# Power_Supply.net
KiCad netlist of a schematic drawn in Altium Designer
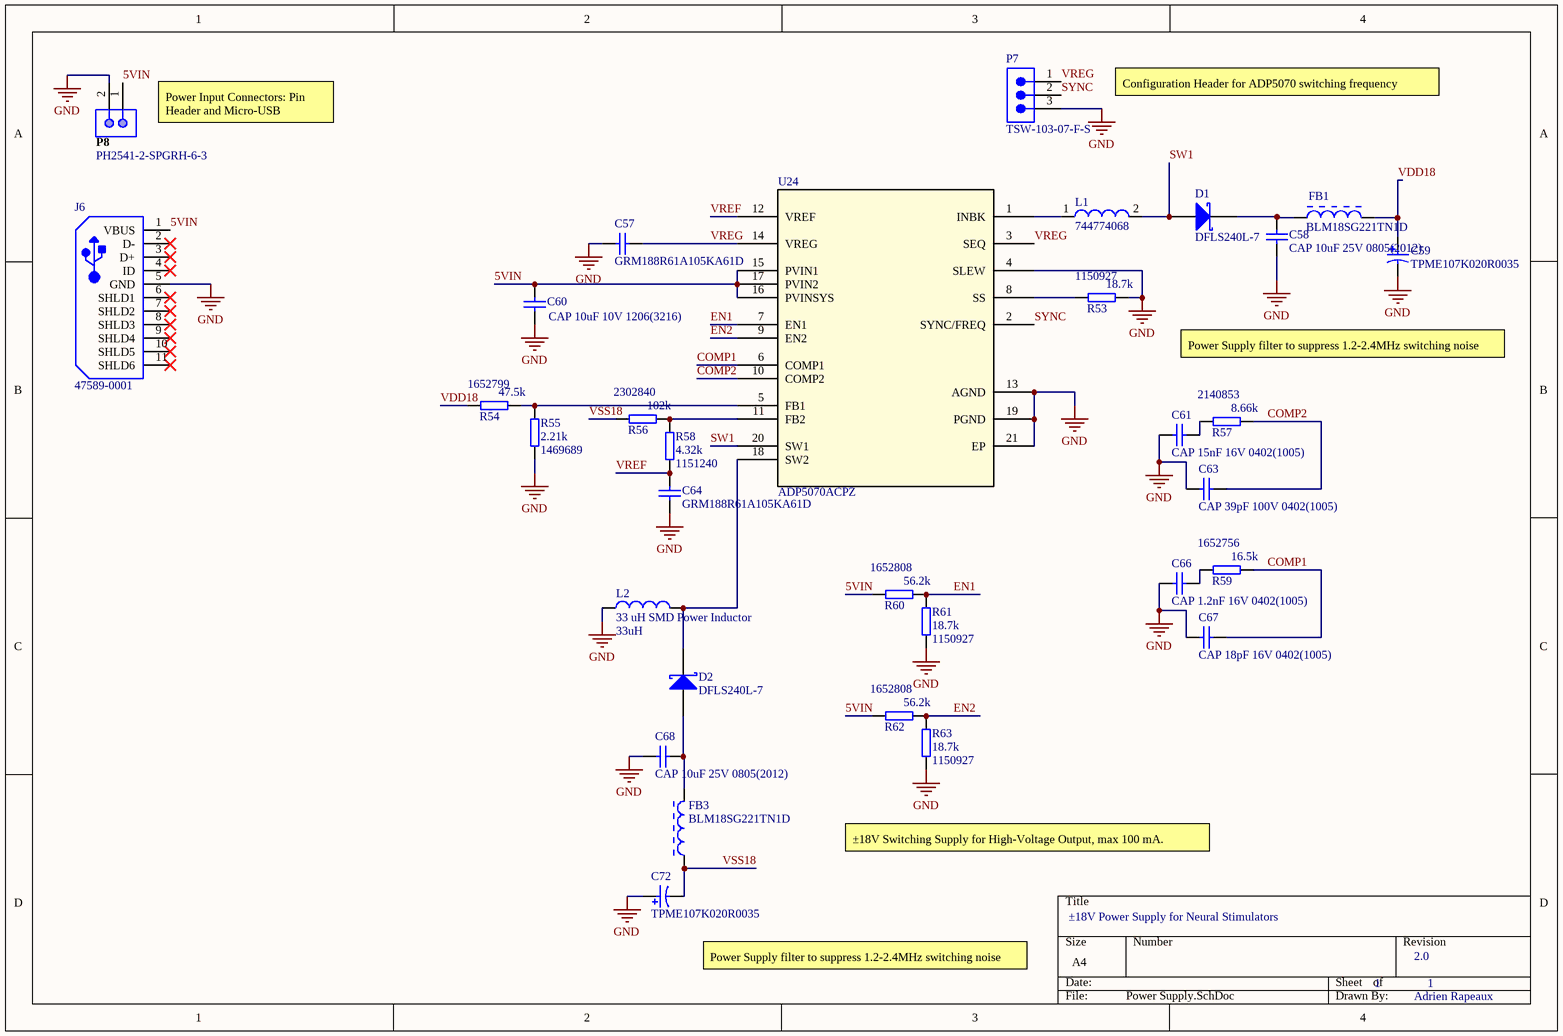
[diagram p0: Power Supply.SchDoc]

(export (version "E")
  (design (tool "Eeschema 10.0.6"))
  (components
    (comp (ref "C57")
      (value "GRM188R61A105KA61D")
      (footprint "CAPC1608X90X35LL10T15")
      (description "Chip Capacitor, 1 uF, +/- 10%, 10 V, -55 to 85 degC, 0603 (1608 Metric), RoHS, Tape and Reel")
      (fields (field (name "MANUFACTURER") "Murata") (field (name "TOLERANCE") "10%"))
      (libsource (lib "Altium Content Vault") (part "CAP-NP-2"))
    )
    (comp (ref "C58")
      (value "CAP 10uF 25V 0805(2012)")
      (footprint "CAPC0805(2012)145_N")
      (description "CAP 10uF 25V ±10% 0805 (2012 Metric) Thickness 1.45mm SMD")
      (fields (field (name "TOLERANCE") "Â±10%"))
      (libsource (lib "Altium Content Vault") (part "CAP"))
    )
    (comp (ref "C59")
      (value "TPME107K020R0035")
      (footprint "CAPMP7344X31-T_V")
      (description "Low ESR, 100 uF, 25 V, +/- 10%, -55 to 125 degC, 2-Pin SMD, RoHS, Tape and Reel")
      (fields (field (name "TOLERANCE") "20%") (field (name "MANUFACTURER") "AVX"))
      (libsource (lib "Altium Content Vault") (part "CAP-P-2"))
    )
    (comp (ref "C60")
      (value "CAP 10uF 10V 1206(3216)")
      (footprint "CAPC1206(3216)130_L")
      (description "CAP 10uF 10V -20% to +80% 1206 (3216 Metric) Thickness 1.3mm SMD")
      (fields (field (name "TOLERANCE") "-20% to +80%"))
      (libsource (lib "Altium Content Vault") (part "CAP"))
    )
    (comp (ref "C61")
      (value "CAP 15nF 16V 0402(1005)")
      (footprint "CAPC0402(1005)60_L")
      (description "CAP 15nF 16V ±10% 0402 (1005 Metric) Thickness 0.6mm SMD")
      (fields (field (name "TOLERANCE") "Â±10%"))
      (libsource (lib "Altium Content Vault") (part "CAP"))
    )
    (comp (ref "C63")
      (value "CAP 39pF 100V 0402(1005)")
      (footprint "CAPC0402(1005)60_L")
      (description "CAP 39pF 100V ±10% 0402 (1005 Metric) Thickness 0.6mm SMD")
      (fields (field (name "TOLERANCE") "Â±10%"))
      (libsource (lib "Altium Content Vault") (part "CAP"))
    )
    (comp (ref "C64")
      (value "GRM188R61A105KA61D")
      (footprint "CAPC1608X90X35LL10T15")
      (description "Chip Capacitor, 1 uF, +/- 10%, 10 V, -55 to 85 degC, 0603 (1608 Metric), RoHS, Tape and Reel")
      (fields (field (name "MANUFACTURER") "Murata") (field (name "TOLERANCE") "10%"))
      (libsource (lib "Altium Content Vault") (part "CAP-NP-2"))
    )
    (comp (ref "C66")
      (value "CAP 1.2nF 16V 0402(1005)")
      (footprint "CAPC0402(1005)60_L")
      (description "CAP 1.2nF 16V ±10% 0402 (1005 Metric) Thickness 0.6mm SMD")
      (fields (field (name "TOLERANCE") "Â±10%"))
      (libsource (lib "Altium Content Vault") (part "CAP"))
    )
    (comp (ref "C67")
      (value "CAP 18pF 16V 0402(1005)")
      (footprint "CAPC0402(1005)60_L")
      (description "CAP 18pF 16V ±10% 0402 (1005 Metric) Thickness 0.6mm SMD")
      (fields (field (name "TOLERANCE") "Â±10%"))
      (libsource (lib "Altium Content Vault") (part "CAP"))
    )
    (comp (ref "C68")
      (value "CAP 10uF 25V 0805(2012)")
      (footprint "CAPC0805(2012)145_N")
      (description "CAP 10uF 25V ±10% 0805 (2012 Metric) Thickness 1.45mm SMD")
      (fields (field (name "TOLERANCE") "Â±10%"))
      (libsource (lib "Altium Content Vault") (part "CAP"))
    )
    (comp (ref "C72")
      (value "TPME107K020R0035")
      (footprint "CAPMP7344X31-T_V")
      (description "Low ESR, 100 uF, 25 V, +/- 10%, -55 to 125 degC, 2-Pin SMD, RoHS, Tape and Reel")
      (fields (field (name "TOLERANCE") "20%") (field (name "MANUFACTURER") "AVX"))
      (libsource (lib "Altium Content Vault") (part "CAP-P-2"))
    )
    (comp (ref "D1")
      (value "DFLS240L-7")
      (footprint "DIOD-POWERDI123-2_A_V")
      (description "Low VF Schottky Barrier Rectifier, 2 A, 40 V, -55 to 125 degC, 2-Pin SMD, RoHS, Tape and Reel")
      (fields (field (name "MANUFACTURER") "Diodes Inc"))
      (libsource (lib "Altium Content Vault") (part "DSKY-AK-2"))
    )
    (comp (ref "D2")
      (value "DFLS240L-7")
      (footprint "DIOD-POWERDI123-2_A_V")
      (description "Low VF Schottky Barrier Rectifier, 2 A, 40 V, -55 to 125 degC, 2-Pin SMD, RoHS, Tape and Reel")
      (fields (field (name "MANUFACTURER") "Diodes Inc"))
      (libsource (lib "Altium Content Vault") (part "DSKY-AK-2"))
    )
    (comp (ref "FB1")
      (value "BLM18SG221TN1D")
      (footprint "MURA-BLM18SG-B25-CHIP-2_V1")
      (fields (field (name "MANUFACTURER") "Murata"))
      (libsource (lib "Altium Content Vault") (part "MURA-FB-2"))
    )
    (comp (ref "FB3")
      (value "BLM18SG221TN1D")
      (footprint "MURA-BLM18SG-B25-CHIP-2_V1")
      (fields (field (name "MANUFACTURER") "Murata"))
      (libsource (lib "Altium Content Vault") (part "MURA-FB-2"))
    )
    (comp (ref "J6")
      (value "47589-0001")
      (footprint "MOLX-47589-0001_V")
      (description "Right Angle Female Type AB Micro USB Connector, 30 V, 1.8 A, -30 to 85 degC, RoHS, Tape and Reel")
      (fields (field (name "MANUFACTURER") "Molex"))
      (libsource (lib "Altium Content Vault") (part "USB-5-6SHLD"))
    )
    (comp (ref "L1")
      (value "744774068")
      (footprint "WE-PD2-M")
      (description "SMD Power Inductor WE-PD2, L = 6.80 µH")
      (libsource (lib "Altium Content Vault") (part "PAS-IND-INDUCTOR-2"))
    )
    (comp (ref "L2")
      (value "33 uH SMD Power Inductor")
      (footprint "LPS6235 SERIES")
      (description "33 uH SMD Power Inductor, 1A RMS, 1.4A Isat, Shielded, LPS6235 Series, Coilcraft")
      (fields (field (name "ALTIUM_VALUE") "33uH") (field (name "PUBLISHER") "Adrien Rapeaux"))
      (libsource (lib "ar5113_Altium_Library") (part "LPS6235-333MRB"))
    )
    (comp (ref "P7")
      (value "TSW-103-07-F-S")
      (footprint "SMTC-TSW-103-07-X-S")
      (description "0.025\" SQ Post Header, Through-hole, Vertical, -55 to 125 degC, 2.54 mm Pitch, 3-Pin, Male, RoHS")
      (fields (field (name "MANUFACTURER") "Samtec"))
      (libsource (lib "Altium Content Vault") (part "SMTC-TSW-103-X-X-S-X"))
    )
    (comp (ref "P8")
      (value "PH2541-2-SPGRH-6-3")
      (footprint "PH2541-2-SPGRH-6-3_V")
      (description "Male Header, Pitch 2.54mm, 2x1 Position, Mated Height 6mm, Tail Length 3mm")
      (libsource (lib "Altium Content Vault") (part "PCE-HDR-1P-M-R2"))
    )
    (comp (ref "R53")
      (value "18.7k")
      (footprint "RESC0402")
      (description "RES 18K7 0402 0.063W 1%")
      (fields
        (field (name "MANUFACTURER PART NUMBER") "CRCW040218K7FKTDBC")
        (field (name "MANUFACTURER") "VISHAY")
        (field (name "SUPPLIER PART NUMBER 2") "1150927")
      )
      (libsource (lib "Lib_MyProto") (part "myProto-12585"))
    )
    (comp (ref "R54")
      (value "47.5k")
      (footprint "RESC0402")
      (description "RES 47K5 0402 0.063W 1%")
      (fields
        (field (name "MANUFACTURER PART NUMBER") "CRCW040247K5FKTDBC")
        (field (name "MANUFACTURER") "VISHAY")
        (field (name "SUPPLIER PART NUMBER 2") "1652799")
      )
      (libsource (lib "Lib_MyProto") (part "myProto-12633"))
    )
    (comp (ref "R55")
      (value "2.21k")
      (footprint "RESC0402")
      (description "RES 2K21 0402 0.063W 1%")
      (fields
        (field (name "MANUFACTURER PART NUMBER") "CRCW04022K21FKTDBC")
        (field (name "MANUFACTURER") "VISHAY")
        (field (name "SUPPLIER PART NUMBER 1") "1469689")
      )
      (libsource (lib "Lib_MyProto") (part "myProto-12479"))
    )
    (comp (ref "R56")
      (value "102k")
      (footprint "RESC0402")
      (description "RES 102K 0402 0.063W 1%")
      (fields
        (field (name "MANUFACTURER PART NUMBER") "CRCW0402102KFKTDBC")
        (field (name "MANUFACTURER") "VISHAY")
        (field (name "SUPPLIER PART NUMBER 1") "2302840")
      )
      (libsource (lib "Lib_MyProto") (part "myProto-12671"))
    )
    (comp (ref "R57")
      (value "8.66k")
      (footprint "RESC0402")
      (description "RES 8K66 0402 0.063W 1%")
      (fields
        (field (name "MANUFACTURER PART NUMBER") "CRCW04028K66FKTDBC")
        (field (name "MANUFACTURER") "VISHAY")
        (field (name "SUPPLIER PART NUMBER 1") "2140853")
      )
      (libsource (lib "Lib_MyProto") (part "myProto-12549"))
    )
    (comp (ref "R58")
      (value "4.32k")
      (footprint "RESC0402")
      (description "RES 4K32 0402 0.063W 1%")
      (fields
        (field (name "MANUFACTURER PART NUMBER") "CRCW04024K32FKTDBC")
        (field (name "MANUFACTURER") "VISHAY")
        (field (name "SUPPLIER PART NUMBER 1") "1151240")
      )
      (libsource (lib "Lib_MyProto") (part "myProto-12514"))
    )
    (comp (ref "R59")
      (value "16.5k")
      (footprint "RESC0402")
      (description "RES 16K5 0402 0.063W 1%")
      (fields
        (field (name "MANUFACTURER PART NUMBER") "CRCW040216K5FKTDBC")
        (field (name "MANUFACTURER") "VISHAY")
        (field (name "SUPPLIER PART NUMBER 1") "1652756")
      )
      (libsource (lib "Lib_MyProto") (part "myProto-12579"))
    )
    (comp (ref "R60")
      (value "56.2k")
      (footprint "RESC0402")
      (description "RES 56K2 0402 0.063W 1%")
      (fields
        (field (name "MANUFACTURER PART NUMBER") "CRCW040256K2FKTDBC")
        (field (name "MANUFACTURER") "VISHAY")
        (field (name "SUPPLIER PART NUMBER 1") "1652808")
      )
      (libsource (lib "Lib_MyProto") (part "myProto-12642"))
    )
    (comp (ref "R61")
      (value "18.7k")
      (footprint "RESC0402")
      (description "RES 18K7 0402 0.063W 1%")
      (fields
        (field (name "MANUFACTURER PART NUMBER") "CRCW040218K7FKTDBC")
        (field (name "MANUFACTURER") "VISHAY")
        (field (name "SUPPLIER PART NUMBER 2") "1150927")
      )
      (libsource (lib "Lib_MyProto") (part "myProto-12585"))
    )
    (comp (ref "R62")
      (value "56.2k")
      (footprint "RESC0402")
      (description "RES 56K2 0402 0.063W 1%")
      (fields
        (field (name "MANUFACTURER PART NUMBER") "CRCW040256K2FKTDBC")
        (field (name "MANUFACTURER") "VISHAY")
        (field (name "SUPPLIER PART NUMBER 1") "1652808")
      )
      (libsource (lib "Lib_MyProto") (part "myProto-12642"))
    )
    (comp (ref "R63")
      (value "18.7k")
      (footprint "RESC0402")
      (description "RES 18K7 0402 0.063W 1%")
      (fields
        (field (name "MANUFACTURER PART NUMBER") "CRCW040218K7FKTDBC")
        (field (name "MANUFACTURER") "VISHAY")
        (field (name "SUPPLIER PART NUMBER 2") "1150927")
      )
      (libsource (lib "Lib_MyProto") (part "myProto-12585"))
    )
    (comp (ref "U24")
      (value "ADP5070ACPZ")
      (footprint "CP_20_8")
      (description "Imported")
      (libsource (lib "ar5113_Altium_Library") (part "ADP5070ACPZ"))
    )
  )
  (nets
    (net (code "1") (name "/5VIN") (class "Default")
      (node (ref "C60") (pin "2") (pinfunction "2_2") (pintype "passive"))
      (node (ref "J6") (pin "1") (pinfunction "VBUS_1") (pintype "passive"))
      (node (ref "P8") (pin "1") (pinfunction "1_1") (pintype "passive"))
      (node (ref "R60") (pin "2") (pinfunction "2_2") (pintype "passive"))
      (node (ref "R62") (pin "2") (pinfunction "2_2") (pintype "passive"))
      (node (ref "U24") (pin "15") (pinfunction "PVIN1_15") (pintype "passive"))
      (node (ref "U24") (pin "16") (pinfunction "PVINSYS_16") (pintype "passive"))
      (node (ref "U24") (pin "17") (pinfunction "PVIN2_17") (pintype "passive"))
    )
    (net (code "2") (name "/COMP1") (class "Default")
      (node (ref "C67") (pin "2") (pinfunction "2_2") (pintype "passive"))
      (node (ref "R59") (pin "1") (pinfunction "1_1") (pintype "passive"))
      (node (ref "U24") (pin "6") (pinfunction "COMP1_6") (pintype "passive"))
    )
    (net (code "3") (name "/COMP2") (class "Default")
      (node (ref "C63") (pin "2") (pinfunction "2_2") (pintype "passive"))
      (node (ref "R57") (pin "1") (pinfunction "1_1") (pintype "passive"))
      (node (ref "U24") (pin "10") (pinfunction "COMP2_10") (pintype "passive"))
    )
    (net (code "4") (name "/EN1") (class "Default")
      (node (ref "R60") (pin "1") (pinfunction "1_1") (pintype "passive"))
      (node (ref "R61") (pin "1") (pinfunction "1_1") (pintype "passive"))
      (node (ref "U24") (pin "7") (pinfunction "EN1_7") (pintype "passive"))
    )
    (net (code "5") (name "/EN2") (class "Default")
      (node (ref "R62") (pin "1") (pinfunction "1_1") (pintype "passive"))
      (node (ref "R63") (pin "1") (pinfunction "1_1") (pintype "passive"))
      (node (ref "U24") (pin "9") (pinfunction "EN2_9") (pintype "passive"))
    )
    (net (code "6") (name "/SW1") (class "Default")
      (node (ref "D1") (pin "1") (pinfunction "A_1") (pintype "passive"))
      (node (ref "L1") (pin "2") (pinfunction "2_2") (pintype "passive"))
      (node (ref "U24") (pin "20") (pinfunction "SW1_20") (pintype "passive"))
    )
    (net (code "7") (name "/SYNC") (class "Default")
      (node (ref "P7") (pin "2") (pinfunction "2_2") (pintype "passive"))
      (node (ref "U24") (pin "2") (pinfunction "SYNC/FREQ_2") (pintype "passive"))
    )
    (net (code "8") (name "/VDD18") (class "Default")
      (node (ref "C59") (pin "1") (pinfunction "1_1") (pintype "passive"))
      (node (ref "FB1") (pin "2") (pinfunction "2_2") (pintype "passive"))
      (node (ref "R54") (pin "2") (pinfunction "2_2") (pintype "passive"))
    )
    (net (code "9") (name "/VREF") (class "Default")
      (node (ref "C64") (pin "2") (pinfunction "2_2") (pintype "passive"))
      (node (ref "R58") (pin "2") (pinfunction "2_2") (pintype "passive"))
      (node (ref "U24") (pin "12") (pinfunction "VREF_12") (pintype "passive"))
    )
    (net (code "10") (name "/VREG") (class "Default")
      (node (ref "C57") (pin "2") (pinfunction "2_2") (pintype "passive"))
      (node (ref "P7") (pin "1") (pinfunction "1_1") (pintype "passive"))
      (node (ref "U24") (pin "14") (pinfunction "VREG_14") (pintype "passive"))
      (node (ref "U24") (pin "3") (pinfunction "SEQ_3") (pintype "passive"))
    )
    (net (code "11") (name "/VSS18") (class "Default")
      (node (ref "C72") (pin "2") (pinfunction "2_2") (pintype "passive"))
      (node (ref "FB3") (pin "1") (pinfunction "1_1") (pintype "passive"))
      (node (ref "R56") (pin "2") (pinfunction "2_2") (pintype "passive"))
    )
    (net (code "12") (name "GND") (class "Default")
      (node (ref "C57") (pin "1") (pinfunction "1_1") (pintype "passive"))
      (node (ref "C58") (pin "1") (pinfunction "1_1") (pintype "passive"))
      (node (ref "C59") (pin "2") (pinfunction "2_2") (pintype "passive"))
      (node (ref "C60") (pin "1") (pinfunction "1_1") (pintype "passive"))
      (node (ref "C61") (pin "1") (pinfunction "1_1") (pintype "passive"))
      (node (ref "C63") (pin "1") (pinfunction "1_1") (pintype "passive"))
      (node (ref "C64") (pin "1") (pinfunction "1_1") (pintype "passive"))
      (node (ref "C66") (pin "1") (pinfunction "1_1") (pintype "passive"))
      (node (ref "C67") (pin "1") (pinfunction "1_1") (pintype "passive"))
      (node (ref "C68") (pin "1") (pinfunction "1_1") (pintype "passive"))
      (node (ref "C72") (pin "1") (pinfunction "1_1") (pintype "passive"))
      (node (ref "J6") (pin "5") (pinfunction "GND_5") (pintype "passive"))
      (node (ref "L2") (pin "1") (pinfunction "1_1") (pintype "passive"))
      (node (ref "P7") (pin "3") (pinfunction "3_3") (pintype "passive"))
      (node (ref "P8") (pin "2") (pinfunction "2_2") (pintype "passive"))
      (node (ref "R53") (pin "1") (pinfunction "1_1") (pintype "passive"))
      (node (ref "R55") (pin "2") (pinfunction "2_2") (pintype "passive"))
      (node (ref "R61") (pin "2") (pinfunction "2_2") (pintype "passive"))
      (node (ref "R63") (pin "2") (pinfunction "2_2") (pintype "passive"))
      (node (ref "U24") (pin "13") (pinfunction "AGND_13") (pintype "passive"))
      (node (ref "U24") (pin "19") (pinfunction "PGND_19") (pintype "passive"))
      (node (ref "U24") (pin "21") (pinfunction "EP_21") (pintype "passive"))
      (node (ref "U24") (pin "4") (pinfunction "SLEW_4") (pintype "passive"))
    )
    (net (code "13") (name "Net-(C61-Pad2)") (class "Default")
      (node (ref "C61") (pin "2") (pinfunction "2_2") (pintype "passive"))
      (node (ref "R57") (pin "2") (pinfunction "2_2") (pintype "passive"))
    )
    (net (code "14") (name "Net-(C66-Pad2)") (class "Default")
      (node (ref "C66") (pin "2") (pinfunction "2_2") (pintype "passive"))
      (node (ref "R59") (pin "2") (pinfunction "2_2") (pintype "passive"))
    )
    (net (code "15") (name "Net-(D1-K)") (class "Default")
      (node (ref "C58") (pin "2") (pinfunction "2_2") (pintype "passive"))
      (node (ref "D1") (pin "2") (pinfunction "K_2") (pintype "passive"))
      (node (ref "FB1") (pin "1") (pinfunction "1_1") (pintype "passive"))
    )
    (net (code "16") (name "Net-(D2-A)") (class "Default")
      (node (ref "C68") (pin "2") (pinfunction "2_2") (pintype "passive"))
      (node (ref "D2") (pin "1") (pinfunction "A_1") (pintype "passive"))
      (node (ref "FB3") (pin "2") (pinfunction "2_2") (pintype "passive"))
    )
    (net (code "17") (name "Net-(D2-K)") (class "Default")
      (node (ref "D2") (pin "2") (pinfunction "K_2") (pintype "passive"))
      (node (ref "L2") (pin "2") (pinfunction "2_2") (pintype "passive"))
      (node (ref "U24") (pin "18") (pinfunction "SW2_18") (pintype "passive"))
    )
    (net (code "18") (name "Net-(U24-FB1)") (class "Default")
      (node (ref "R54") (pin "1") (pinfunction "1_1") (pintype "passive"))
      (node (ref "R55") (pin "1") (pinfunction "1_1") (pintype "passive"))
      (node (ref "U24") (pin "5") (pinfunction "FB1_5") (pintype "passive"))
    )
    (net (code "19") (name "Net-(U24-FB2)") (class "Default")
      (node (ref "R56") (pin "1") (pinfunction "1_1") (pintype "passive"))
      (node (ref "R58") (pin "1") (pinfunction "1_1") (pintype "passive"))
      (node (ref "U24") (pin "11") (pinfunction "FB2_11") (pintype "passive"))
    )
    (net (code "20") (name "Net-(U24-INBK)") (class "Default")
      (node (ref "L1") (pin "1") (pinfunction "1_1") (pintype "passive"))
      (node (ref "U24") (pin "1") (pinfunction "INBK_1") (pintype "passive"))
    )
    (net (code "21") (name "Net-(U24-SS)") (class "Default")
      (node (ref "R53") (pin "2") (pinfunction "2_2") (pintype "passive"))
      (node (ref "U24") (pin "8") (pinfunction "SS_8") (pintype "passive"))
    )
    (net (code "22") (name "unconnected-(J6-D+-Pad3)") (class "Default")
      (node (ref "J6") (pin "3") (pinfunction "D+_3") (pintype "passive+no_connect"))
    )
    (net (code "23") (name "unconnected-(J6-D--Pad2)") (class "Default")
      (node (ref "J6") (pin "2") (pinfunction "D-_2") (pintype "passive+no_connect"))
    )
    (net (code "24") (name "unconnected-(J6-ID-Pad4)") (class "Default")
      (node (ref "J6") (pin "4") (pinfunction "ID_4") (pintype "passive+no_connect"))
    )
    (net (code "25") (name "unconnected-(J6-SHLD1-Pad6)") (class "Default")
      (node (ref "J6") (pin "6") (pinfunction "SHLD1_6") (pintype "passive+no_connect"))
    )
    (net (code "26") (name "unconnected-(J6-SHLD2-Pad7)") (class "Default")
      (node (ref "J6") (pin "7") (pinfunction "SHLD2_7") (pintype "passive+no_connect"))
    )
    (net (code "27") (name "unconnected-(J6-SHLD3-Pad8)") (class "Default")
      (node (ref "J6") (pin "8") (pinfunction "SHLD3_8") (pintype "passive+no_connect"))
    )
    (net (code "28") (name "unconnected-(J6-SHLD4-Pad9)") (class "Default")
      (node (ref "J6") (pin "9") (pinfunction "SHLD4_9") (pintype "passive+no_connect"))
    )
    (net (code "29") (name "unconnected-(J6-SHLD5-Pad10)") (class "Default")
      (node (ref "J6") (pin "10") (pinfunction "SHLD5_10") (pintype "passive+no_connect"))
    )
    (net (code "30") (name "unconnected-(J6-SHLD6-Pad11)") (class "Default")
      (node (ref "J6") (pin "11") (pinfunction "SHLD6_11") (pintype "passive+no_connect"))
    )
  )
)
